# ProDoc_UI_2025-10-13.net
KiCad netlist of a schematic drawn in EasyEDA Pro
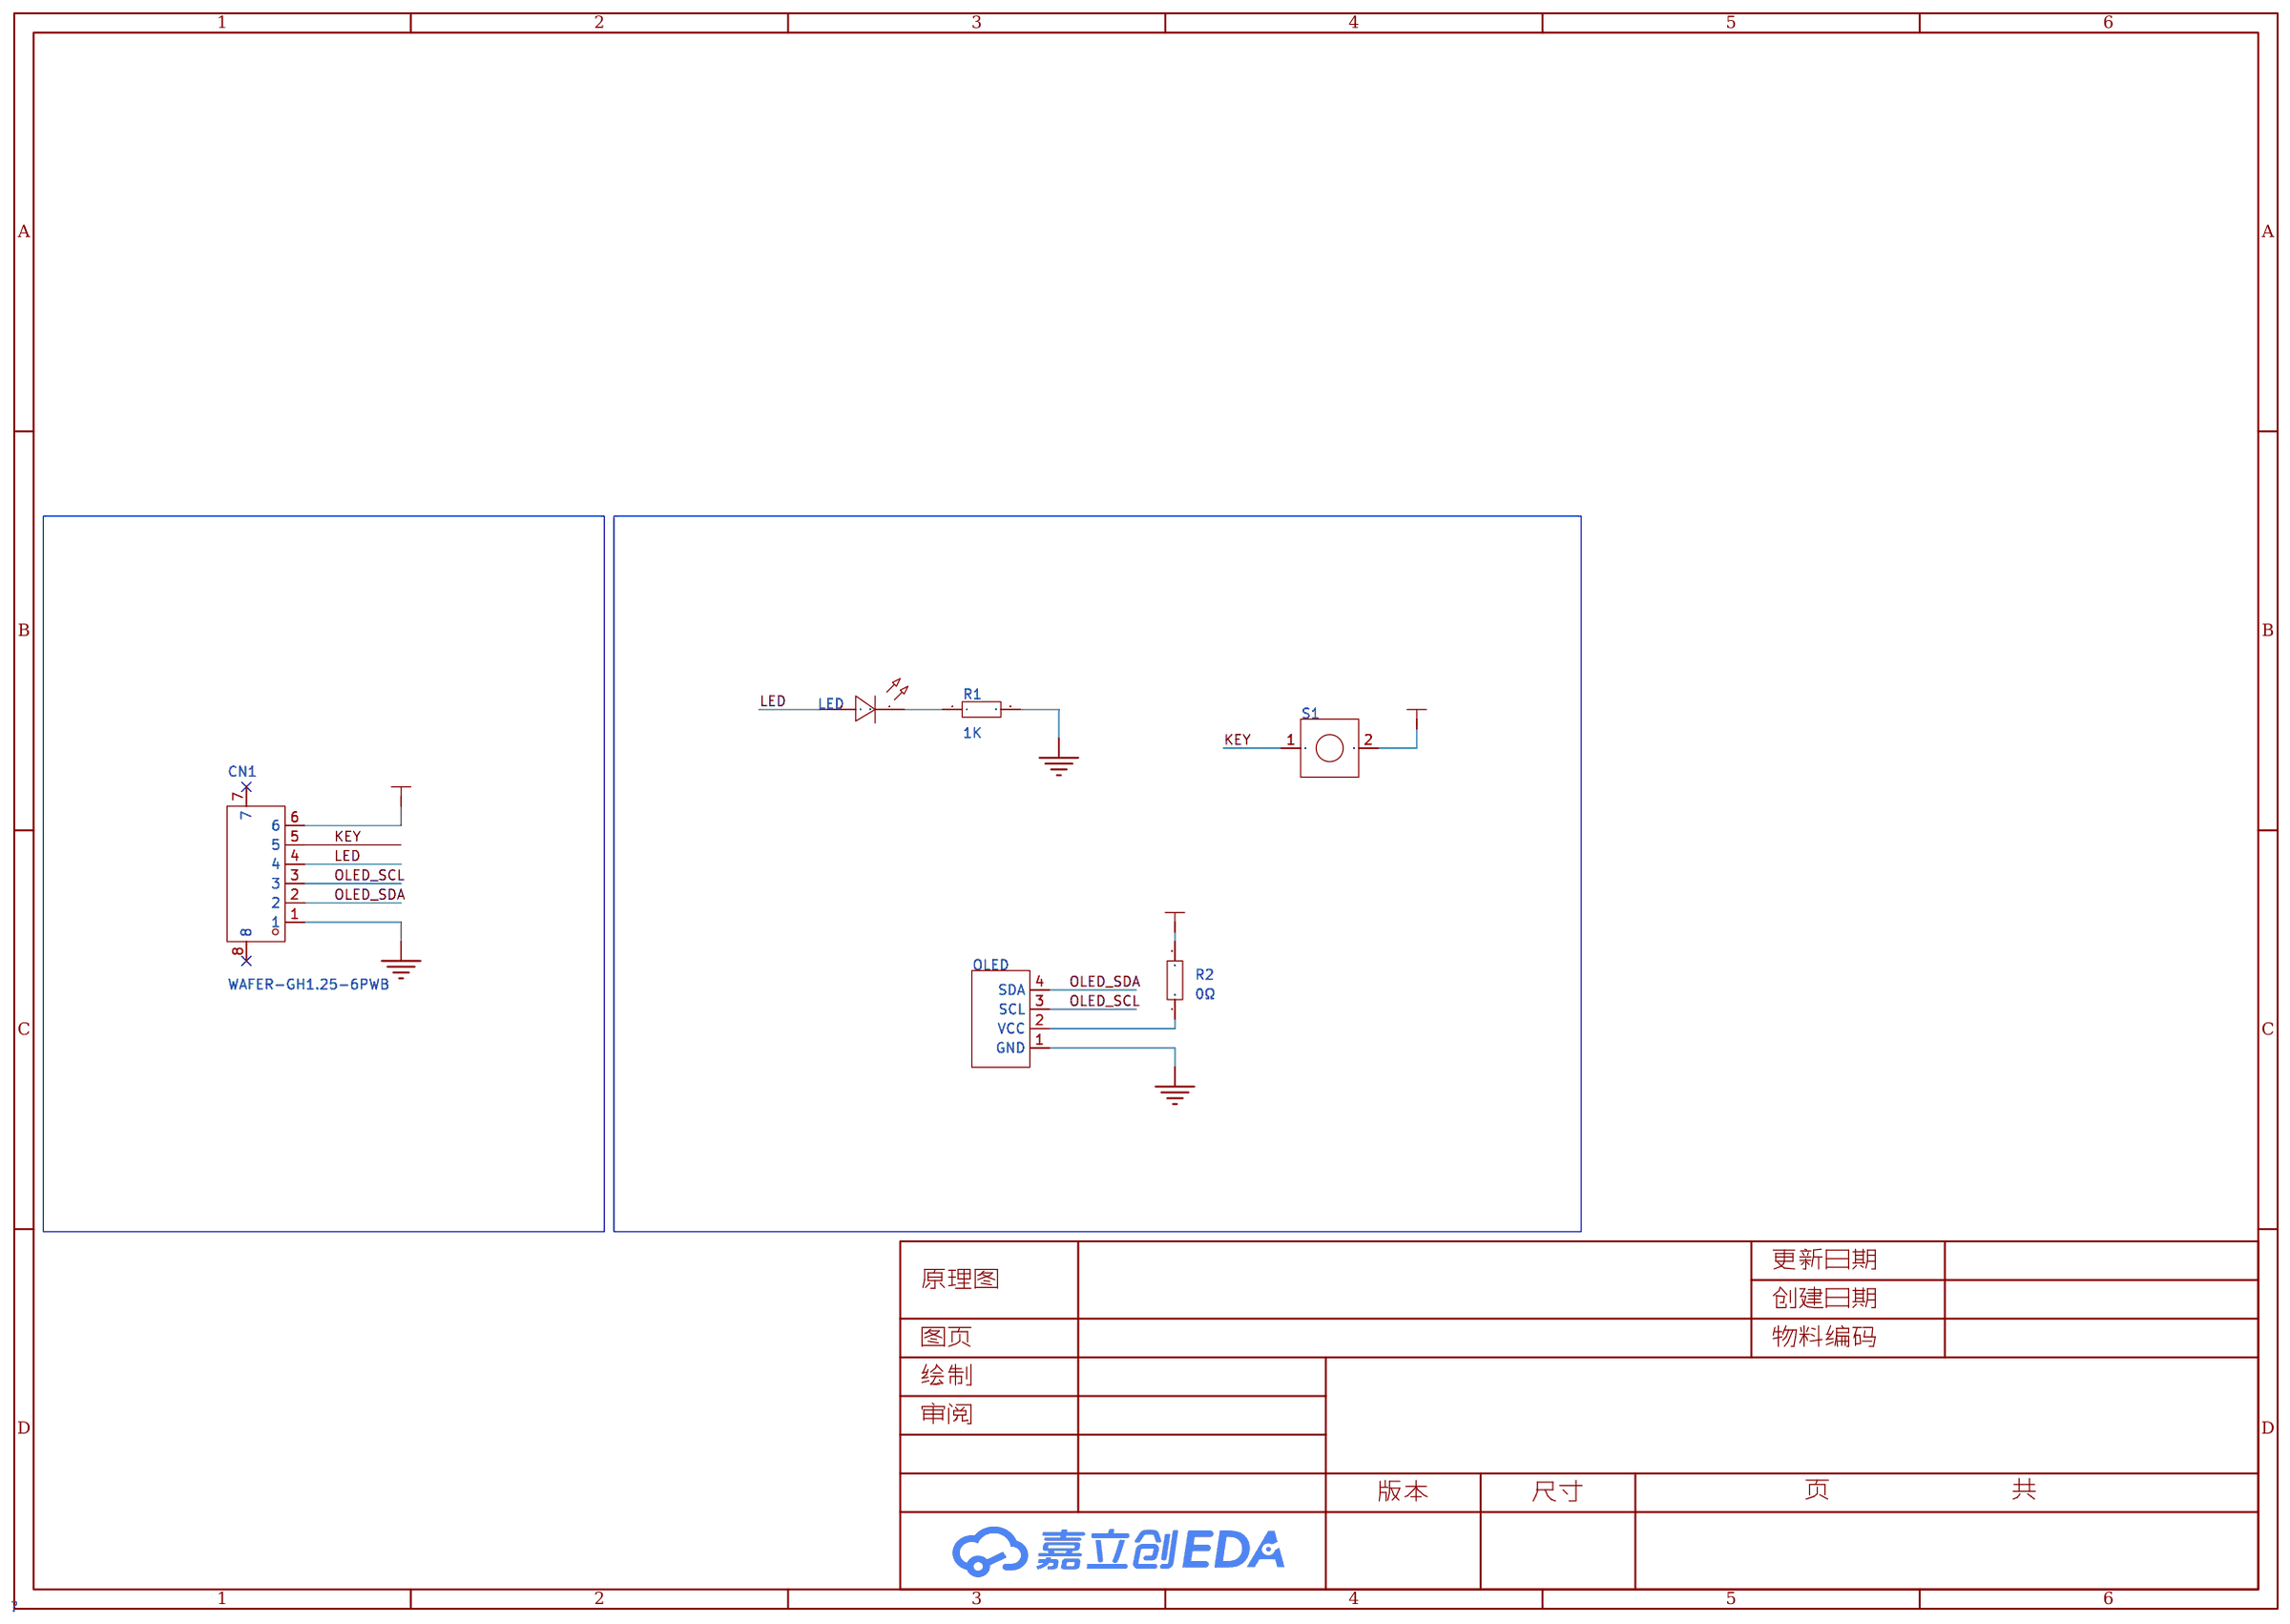
[diagram p0: schematic sheet]

(export (version "E")
  (design (tool "Eeschema 10.0.6"))
  (components
    (comp (ref "CN1")
      (value "WAFER-GH1.25-6PWB")
      (footprint "easyedapro:CONN-SMD_6P-P1.25_XUNPU_WAFER-GH1.25-6PWB")
      (fields (field (name "Manufacturer") "XUNPU(讯普)"))
      (libsource (lib "easyedapro") (part "WAFER-GH1.25-6PWB"))
    )
    (comp (ref "LED")
      (value "~")
      (footprint "easyedapro:LED0603")
      (libsource (lib "easyedapro") (part "LED0603-WHITE"))
    )
    (comp (ref "OLED")
      (value "~")
      (footprint "easyedapro:MOULD-OLED-0.91-12832-I2C-SSD1306")
      (libsource (lib "easyedapro") (part "模组-OLED-0.91-12832-I2C-SSD1306"))
    )
    (comp (ref "R1")
      (value "1K")
      (footprint "easyedapro:R0603")
      (libsource (lib "easyedapro") (part "R0603"))
    )
    (comp (ref "R2")
      (value "0Ω")
      (footprint "easyedapro:R0603")
      (libsource (lib "easyedapro") (part "R0603"))
    )
    (comp (ref "S1")
      (value "~")
      (footprint "easyedapro:6*6*5 硅胶开关")
      (libsource (lib "easyedapro") (part "6*6*5 硅胶开关"))
    )
  )
  (nets
    (net (code "1") (name "/KEY") (class "Default")
      (node (ref "CN1") (pin "5") (pinfunction "5_5") (pintype "unspecified"))
      (node (ref "S1") (pin "1") (pinfunction "1_1") (pintype "input"))
    )
    (net (code "2") (name "/LED") (class "Default")
      (node (ref "CN1") (pin "4") (pinfunction "4_4") (pintype "unspecified"))
      (node (ref "LED") (pin "2") (pinfunction "A_2") (pintype "input"))
    )
    (net (code "3") (name "/OLED_SCL") (class "Default")
      (node (ref "CN1") (pin "3") (pinfunction "3_3") (pintype "unspecified"))
      (node (ref "OLED") (pin "3") (pinfunction "SCL_3") (pintype "input"))
    )
    (net (code "4") (name "/OLED_SDA") (class "Default")
      (node (ref "CN1") (pin "2") (pinfunction "2_2") (pintype "unspecified"))
      (node (ref "OLED") (pin "4") (pinfunction "SDA_4") (pintype "input"))
    )
    (net (code "5") (name "5V") (class "Default")
      (node (ref "CN1") (pin "6") (pinfunction "6_6") (pintype "unspecified"))
      (node (ref "R2") (pin "2") (pinfunction "2_2") (pintype "input"))
      (node (ref "S1") (pin "2") (pinfunction "2_2") (pintype "input"))
    )
    (net (code "6") (name "GND") (class "Default")
      (node (ref "CN1") (pin "1") (pinfunction "1_1") (pintype "unspecified"))
      (node (ref "OLED") (pin "1") (pinfunction "GND_1") (pintype "input"))
      (node (ref "R1") (pin "2") (pinfunction "2_2") (pintype "input"))
    )
    (net (code "7") (name "Net-(LED-C)") (class "Default")
      (node (ref "LED") (pin "1") (pinfunction "C_1") (pintype "input"))
      (node (ref "R1") (pin "1") (pinfunction "1_1") (pintype "input"))
    )
    (net (code "8") (name "Net-(OLED-VCC)") (class "Default")
      (node (ref "OLED") (pin "2") (pinfunction "VCC_2") (pintype "input"))
      (node (ref "R2") (pin "1") (pinfunction "1_1") (pintype "input"))
    )
    (net (code "9") (name "unconnected-(CN1-Pad7)") (class "Default")
      (node (ref "CN1") (pin "7") (pinfunction "7_7") (pintype "unspecified+no_connect"))
    )
    (net (code "10") (name "unconnected-(CN1-Pad8)") (class "Default")
      (node (ref "CN1") (pin "8") (pinfunction "8_8") (pintype "unspecified+no_connect"))
    )
  )
)
